# BioTempSch.net
KiCad netlist of a schematic drawn in Altium Designer
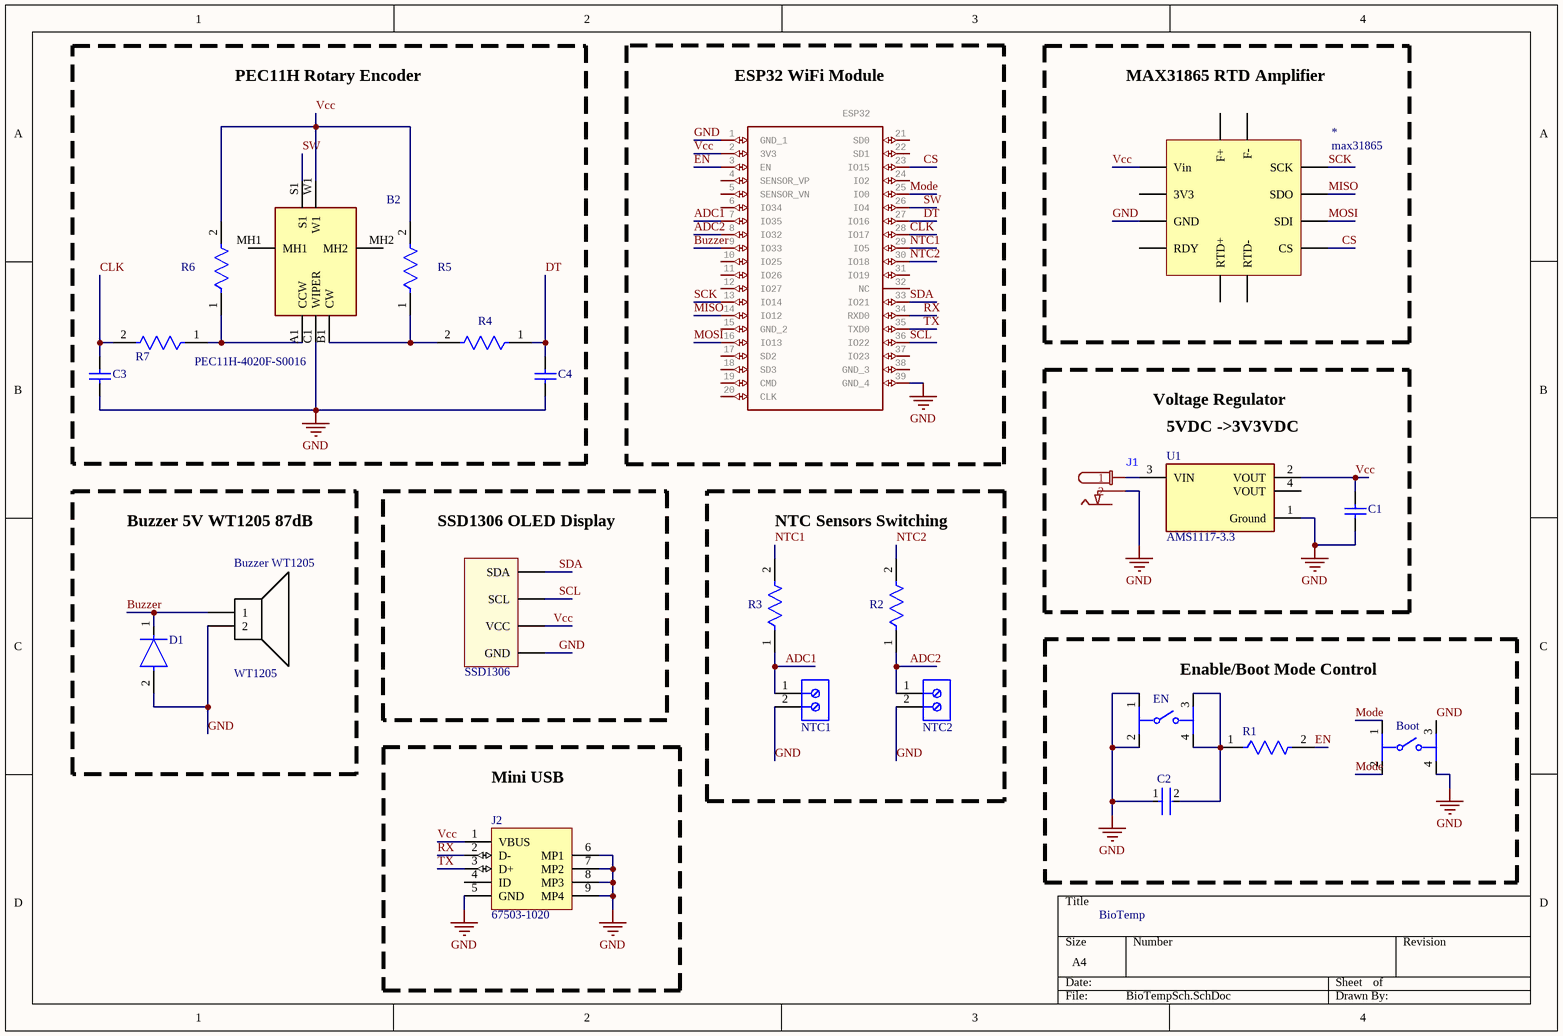
[diagram p0: BioTempSch.SchDoc]

(export (version "E")
  (design (tool "Eeschema 10.0.6"))
  (components
    (comp (ref "*")
      (value "max31865")
      (footprint "max31865")
      (libsource (lib "BioTempSchLib") (part "max31865"))
    )
    (comp (ref "B2")
      (value "PEC11H-4020F-S0016")
      (footprint "PEC11H4020FS0016")
      (description "Encoders ROTARY ENCODER W/BALL SPRING")
      (fields (field (name "MOUSER PART NUMBER") "652-PEC11H4020FS0016"))
      (libsource (lib "PEC11H-4020F-S0016") (part "PEC11H-4020F-S0016"))
    )
    (comp (ref "Boot")
      (value "B3F-1070")
      (footprint "FP-B3F-1070-MFG")
      (description "SWITCH TACTILE SPST-NO 0.05A 24V")
      (libsource (lib "Altium Content Vault") (part "b8895f3f4cefb76e1819d2863dba89b"))
    )
    (comp (ref "Buzzer WT1205")
      (value "WT1205")
      (footprint "WT1205")
      (description "Buzzer WT1205 87dB 5V")
      (libsource (lib "BioTempSchLib") (part "WT1205"))
    )
    (comp (ref "C1")
      (value "C0805C103K5RACTU")
      (footprint "CAPC2013X88X50LL20T25")
      (fields (field (name "MANUFACTURER") "Kemet"))
      (libsource (lib "Altium Content Vault") (part "CAP"))
    )
    (comp (ref "C2")
      (value "C0603C104M4RACTU")
      (footprint "FP-C0603C-CF-MFG")
      (description "CAP CER 0.1UF 16V X7R 0603")
      (fields (field (name "TOLERANCE") "0.2") (field (name "MANUFACTURER") "KEMET"))
      (libsource (lib "Altium Content Vault") (part "b4654b650e69147ec39a6b967a45e02"))
    )
    (comp (ref "C3")
      (value "C0805C103K5RACTU")
      (footprint "CAPC2013X88X50LL20T25")
      (fields (field (name "MANUFACTURER") "Kemet"))
      (libsource (lib "Altium Content Vault") (part "CAP"))
    )
    (comp (ref "C4")
      (value "C0805C103K5RACTU")
      (footprint "CAPC2013X88X50LL20T25")
      (fields (field (name "MANUFACTURER") "Kemet"))
      (libsource (lib "Altium Content Vault") (part "CAP"))
    )
    (comp (ref "D1")
      (value "1N4007 SMD")
      (footprint "FP-1N4007_SMD-IPC_C")
      (description "Rectifier, 1Kv, 1A, Do-214Ac Rohs Compliant: Yes")
      (libsource (lib "Altium Content Vault") (part "d7152d700b627762746794eb795d46e"))
    )
    (comp (ref "EN")
      (value "B3F-1070")
      (footprint "FP-B3F-1070-MFG")
      (description "SWITCH TACTILE SPST-NO 0.05A 24V")
      (libsource (lib "Altium Content Vault") (part "b8895f3f4cefb76e1819d2863dba89b"))
    )
    (comp (ref "ESP32")
      (value "WiFi Modules (802.11) SMD Module, ESP32-D0WD, 32Mbits SPI flash, UART mode, PCB antenna   Source:  Datasheet")
      (footprint "ESP32WROOM32D")
      (fields (field (name "MANUFACTURER_PART_NUMBER") "ESP32-WROOM-32D"))
      (libsource (lib "ESP32-WROOM-32D.Library") (part "ESP32-WROOM-32D"))
    )
    (comp (ref "J1")
      (value "~")
      (footprint "P4 JACK")
      (libsource (lib "altium-import") (part "root_0_POWER JACK P4_"))
    )
    (comp (ref "J2")
      (value "67503-1020")
      (footprint "MOLX-67503-1020_V")
      (description "USB, MINI, SMD, RA KME04-USBMU03A01")
      (fields (field (name "MANUFACTURER") "Molex"))
      (libsource (lib "Altium Content Vault") (part "MOLX-67503-1020"))
    )
    (comp (ref "NTC1")
      (value "691213710002")
      (footprint "691213710002")
      (fields (field (name "VOLTAGE") "300V"))
      (libsource (lib "Altium Content Vault") (part "TBL - 1R - 02P - Screw"))
    )
    (comp (ref "NTC2")
      (value "691213710002")
      (footprint "691213710002")
      (fields (field (name "VOLTAGE") "300V"))
      (libsource (lib "Altium Content Vault") (part "TBL - 1R - 02P - Screw"))
    )
    (comp (ref "R1")
      (value "RC0603FR-0710KL")
      (footprint "FP-RC0603-0_55-IPC_C")
      (description "RES 10K OHM 1% 1/10W 0603")
      (fields (field (name "TOLERANCE") "1%"))
      (libsource (lib "Altium Content Vault") (part "1029c3af85768c4190bb7ad29bc67b5"))
    )
    (comp (ref "R2")
      (value "RC0603FR-0710KL")
      (footprint "FP-RC0603-0_55-IPC_C")
      (description "RES 10K OHM 1% 1/10W 0603")
      (fields (field (name "TOLERANCE") "1%"))
      (libsource (lib "Altium Content Vault") (part "1029c3af85768c4190bb7ad29bc67b5"))
    )
    (comp (ref "R3")
      (value "RC0603FR-0710KL")
      (footprint "FP-RC0603-0_55-IPC_C")
      (description "RES 10K OHM 1% 1/10W 0603")
      (fields (field (name "TOLERANCE") "1%"))
      (libsource (lib "Altium Content Vault") (part "1029c3af85768c4190bb7ad29bc67b5"))
    )
    (comp (ref "R4")
      (value "RC0603FR-0710KL")
      (footprint "FP-RC0603-0_55-IPC_C")
      (description "RES 10K OHM 1% 1/10W 0603")
      (fields (field (name "TOLERANCE") "1%"))
      (libsource (lib "Altium Content Vault") (part "1029c3af85768c4190bb7ad29bc67b5"))
    )
    (comp (ref "R5")
      (value "RC0603FR-0710KL")
      (footprint "FP-RC0603-0_55-IPC_C")
      (description "RES 10K OHM 1% 1/10W 0603")
      (fields (field (name "TOLERANCE") "1%"))
      (libsource (lib "Altium Content Vault") (part "1029c3af85768c4190bb7ad29bc67b5"))
    )
    (comp (ref "R6")
      (value "RC0603FR-0710KL")
      (footprint "FP-RC0603-0_55-IPC_C")
      (description "RES 10K OHM 1% 1/10W 0603")
      (fields (field (name "TOLERANCE") "1%"))
      (libsource (lib "Altium Content Vault") (part "1029c3af85768c4190bb7ad29bc67b5"))
    )
    (comp (ref "R7")
      (value "RC0603FR-0710KL")
      (footprint "FP-RC0603-0_55-IPC_C")
      (description "RES 10K OHM 1% 1/10W 0603")
      (fields (field (name "TOLERANCE") "1%"))
      (libsource (lib "Altium Content Vault") (part "1029c3af85768c4190bb7ad29bc67b5"))
    )
    (comp (ref "SSD1306")
      (value "SSD1306")
      (footprint "SSD1306")
      (description "SSD1306 OLED Display 1280x64")
      (libsource (lib "BioTempSchLib") (part "SSD1306"))
    )
    (comp (ref "U1")
      (value "AMS1117-3.3")
      (footprint "FP-AMS1117-IPC_C")
      (description "LDO Voltage Regulators 1A, 3.3V")
      (fields
        (field (name "OCTOPART") "https://octopart.com/ams1117-3.3-advanced+monolithic+systems-25899300")
        (field (name "MANUFACTURER") "Advanced Monolithic Systems")
      )
      (libsource (lib "Altium Content Vault") (part "8bdbb5f8e77002000e30dd2845d0354"))
    )
  )
  (nets
    (net (code "1") (name "/ADC1") (class "Default")
      (node (ref "ESP32") (pin "7") (pinfunction "IO35_7") (pintype "bidirectional"))
      (node (ref "NTC1") (pin "1") (pinfunction "1_1") (pintype "passive"))
      (node (ref "R3") (pin "1") (pinfunction "1_1") (pintype "passive"))
    )
    (net (code "2") (name "/ADC2") (class "Default")
      (node (ref "ESP32") (pin "8") (pinfunction "IO32_8") (pintype "bidirectional"))
      (node (ref "NTC2") (pin "1") (pinfunction "1_1") (pintype "passive"))
      (node (ref "R2") (pin "1") (pinfunction "1_1") (pintype "passive"))
    )
    (net (code "3") (name "/Buzzer") (class "Default")
      (node (ref "Buzzer WT1205") (pin "1") (pinfunction "1_1") (pintype "passive"))
      (node (ref "D1") (pin "1") (pinfunction "C_1") (pintype "passive"))
      (node (ref "ESP32") (pin "9") (pinfunction "IO33_9") (pintype "bidirectional"))
    )
    (net (code "4") (name "/CLK") (class "Default")
      (node (ref "C3") (pin "2") (pinfunction "2_2") (pintype "passive"))
      (node (ref "ESP32") (pin "28") (pinfunction "IO17_28") (pintype "bidirectional"))
      (node (ref "R7") (pin "2") (pinfunction "2_2") (pintype "passive"))
    )
    (net (code "5") (name "/CS") (class "Default")
      (node (ref "*") (pin "7") (pinfunction "CS_7") (pintype "passive"))
      (node (ref "ESP32") (pin "23") (pinfunction "IO15_23") (pintype "bidirectional"))
    )
    (net (code "6") (name "/DT") (class "Default")
      (node (ref "C4") (pin "2") (pinfunction "2_2") (pintype "passive"))
      (node (ref "ESP32") (pin "27") (pinfunction "IO16_27") (pintype "bidirectional"))
      (node (ref "R4") (pin "1") (pinfunction "1_1") (pintype "passive"))
    )
    (net (code "7") (name "/EN") (class "Default")
      (node (ref "ESP32") (pin "3") (pinfunction "EN_3") (pintype "bidirectional"))
      (node (ref "R1") (pin "2") (pinfunction "2_2") (pintype "passive"))
    )
    (net (code "8") (name "/MISO") (class "Default")
      (node (ref "*") (pin "5") (pinfunction "SDO_5") (pintype "passive"))
      (node (ref "ESP32") (pin "14") (pinfunction "IO12_14") (pintype "bidirectional"))
    )
    (net (code "9") (name "/MOSI") (class "Default")
      (node (ref "*") (pin "6") (pinfunction "SDI_6") (pintype "passive"))
      (node (ref "ESP32") (pin "16") (pinfunction "IO13_16") (pintype "bidirectional"))
    )
    (net (code "10") (name "/Mode") (class "Default")
      (node (ref "Boot") (pin "1") (pinfunction "1_1") (pintype "passive"))
      (node (ref "Boot") (pin "2") (pinfunction "2_2") (pintype "passive"))
      (node (ref "ESP32") (pin "25") (pinfunction "IO0_25") (pintype "bidirectional"))
    )
    (net (code "11") (name "/NTC1") (class "Default")
      (node (ref "ESP32") (pin "29") (pinfunction "IO5_29") (pintype "bidirectional"))
      (node (ref "R3") (pin "2") (pinfunction "2_2") (pintype "passive"))
    )
    (net (code "12") (name "/NTC2") (class "Default")
      (node (ref "ESP32") (pin "30") (pinfunction "IO18_30") (pintype "bidirectional"))
      (node (ref "R2") (pin "2") (pinfunction "2_2") (pintype "passive"))
    )
    (net (code "13") (name "/RX") (class "Default")
      (node (ref "ESP32") (pin "34") (pinfunction "RXD0_34") (pintype "bidirectional"))
      (node (ref "J2") (pin "2") (pinfunction "D-_2") (pintype "bidirectional"))
    )
    (net (code "14") (name "/SCK") (class "Default")
      (node (ref "*") (pin "4") (pinfunction "SCK_4") (pintype "passive"))
      (node (ref "ESP32") (pin "13") (pinfunction "IO14_13") (pintype "bidirectional"))
    )
    (net (code "15") (name "/SCL") (class "Default")
      (node (ref "ESP32") (pin "36") (pinfunction "IO22_36") (pintype "bidirectional"))
      (node (ref "SSD1306") (pin "2") (pinfunction "SCL_2") (pintype "passive"))
    )
    (net (code "16") (name "/SDA") (class "Default")
      (node (ref "ESP32") (pin "33") (pinfunction "IO21_33") (pintype "bidirectional"))
      (node (ref "SSD1306") (pin "3") (pinfunction "SDA_3") (pintype "passive"))
    )
    (net (code "17") (name "/SW") (class "Default")
      (node (ref "B2") (pin "S1") (pinfunction "S1_S1") (pintype "passive"))
      (node (ref "ESP32") (pin "26") (pinfunction "IO4_26") (pintype "bidirectional"))
    )
    (net (code "18") (name "/TX") (class "Default")
      (node (ref "ESP32") (pin "35") (pinfunction "TXD0_35") (pintype "bidirectional"))
      (node (ref "J2") (pin "3") (pinfunction "D+_3") (pintype "bidirectional"))
    )
    (net (code "19") (name "/Vcc") (class "Default")
      (node (ref "*") (pin "1") (pinfunction "Vin_1") (pintype "passive"))
      (node (ref "B2") (pin "W1") (pinfunction "W1_W1") (pintype "passive"))
      (node (ref "C1") (pin "2") (pinfunction "2_2") (pintype "passive"))
      (node (ref "ESP32") (pin "2") (pinfunction "3V3_2") (pintype "bidirectional"))
      (node (ref "J2") (pin "1") (pinfunction "VBUS_1") (pintype "power_in"))
      (node (ref "R5") (pin "2") (pinfunction "2_2") (pintype "passive"))
      (node (ref "R6") (pin "2") (pinfunction "2_2") (pintype "passive"))
      (node (ref "SSD1306") (pin "1") (pinfunction "VCC_1") (pintype "passive"))
      (node (ref "U1") (pin "2") (pinfunction "VOUT_2") (pintype "passive"))
    )
    (net (code "20") (name "GND") (class "Default")
      (node (ref "*") (pin "2") (pinfunction "GND_2") (pintype "passive"))
      (node (ref "B2") (pin "C1") (pinfunction "WIPER_C1") (pintype "passive"))
      (node (ref "Boot") (pin "3") (pinfunction "3_3") (pintype "passive"))
      (node (ref "Boot") (pin "4") (pinfunction "4_4") (pintype "passive"))
      (node (ref "Buzzer WT1205") (pin "2") (pinfunction "2_2") (pintype "passive"))
      (node (ref "C1") (pin "1") (pinfunction "1_1") (pintype "passive"))
      (node (ref "C2") (pin "1") (pinfunction "1_1") (pintype "passive"))
      (node (ref "C3") (pin "1") (pinfunction "1_1") (pintype "passive"))
      (node (ref "C4") (pin "1") (pinfunction "1_1") (pintype "passive"))
      (node (ref "D1") (pin "2") (pinfunction "A_2") (pintype "passive"))
      (node (ref "EN") (pin "1") (pinfunction "1_1") (pintype "passive"))
      (node (ref "EN") (pin "2") (pinfunction "2_2") (pintype "passive"))
      (node (ref "ESP32") (pin "1") (pinfunction "GND_1_1") (pintype "bidirectional"))
      (node (ref "ESP32") (pin "39") (pinfunction "GND_4_39") (pintype "bidirectional"))
      (node (ref "J1") (pin "2") (pinfunction "2_2") (pintype "passive"))
      (node (ref "J2") (pin "5") (pinfunction "GND_5") (pintype "power_in"))
      (node (ref "J2") (pin "6") (pinfunction "MP1_6") (pintype "passive"))
      (node (ref "J2") (pin "7") (pinfunction "MP2_7") (pintype "passive"))
      (node (ref "J2") (pin "8") (pinfunction "MP3_8") (pintype "passive"))
      (node (ref "J2") (pin "9") (pinfunction "MP4_9") (pintype "passive"))
      (node (ref "NTC1") (pin "2") (pinfunction "2_2") (pintype "passive"))
      (node (ref "NTC2") (pin "2") (pinfunction "2_2") (pintype "passive"))
      (node (ref "SSD1306") (pin "0") (pinfunction "GND_0") (pintype "passive"))
      (node (ref "U1") (pin "1") (pinfunction "Ground_1") (pintype "power_in"))
    )
    (net (code "21") (name "Net-(B2-CCW)") (class "Default")
      (node (ref "B2") (pin "A1") (pinfunction "CCW_A1") (pintype "passive"))
      (node (ref "R6") (pin "1") (pinfunction "1_1") (pintype "passive"))
      (node (ref "R7") (pin "1") (pinfunction "1_1") (pintype "passive"))
    )
    (net (code "22") (name "Net-(B2-CW)") (class "Default")
      (node (ref "B2") (pin "B1") (pinfunction "CW_B1") (pintype "passive"))
      (node (ref "R4") (pin "2") (pinfunction "2_2") (pintype "passive"))
      (node (ref "R5") (pin "1") (pinfunction "1_1") (pintype "passive"))
    )
    (net (code "23") (name "Net-(C2-Pad2)") (class "Default")
      (node (ref "C2") (pin "2") (pinfunction "2_2") (pintype "passive"))
      (node (ref "EN") (pin "3") (pinfunction "3_3") (pintype "passive"))
      (node (ref "EN") (pin "4") (pinfunction "4_4") (pintype "passive"))
      (node (ref "R1") (pin "1") (pinfunction "1_1") (pintype "passive"))
    )
    (net (code "24") (name "Net-(U1-VIN)") (class "Default")
      (node (ref "J1") (pin "1") (pinfunction "1_1") (pintype "passive"))
      (node (ref "U1") (pin "3") (pinfunction "VIN_3") (pintype "power_in"))
    )
    (net (code "25") (name "unconnected-(*-3V3-Pad3)") (class "Default")
      (node (ref "*") (pin "3") (pinfunction "3V3_3") (pintype "passive"))
    )
    (net (code "26") (name "unconnected-(*-F+-Pad11)") (class "Default")
      (node (ref "*") (pin "11") (pinfunction "F+_11") (pintype "passive"))
    )
    (net (code "27") (name "unconnected-(*-F--Pad12)") (class "Default")
      (node (ref "*") (pin "12") (pinfunction "F-_12") (pintype "passive"))
    )
    (net (code "28") (name "unconnected-(*-RDY-Pad8)") (class "Default")
      (node (ref "*") (pin "8") (pinfunction "RDY_8") (pintype "passive"))
    )
    (net (code "29") (name "unconnected-(*-RTD+-Pad9)") (class "Default")
      (node (ref "*") (pin "9") (pinfunction "RTD+_9") (pintype "passive"))
    )
    (net (code "30") (name "unconnected-(*-RTD--Pad10)") (class "Default")
      (node (ref "*") (pin "10") (pinfunction "RTD-_10") (pintype "passive"))
    )
    (net (code "31") (name "unconnected-(B2-PadMH1)") (class "Default")
      (node (ref "B2") (pin "MH1") (pinfunction "MH1_MH1") (pintype "passive"))
    )
    (net (code "32") (name "unconnected-(B2-PadMH2)") (class "Default")
      (node (ref "B2") (pin "MH2") (pinfunction "MH2_MH2") (pintype "passive"))
    )
    (net (code "33") (name "unconnected-(ESP32-CLK-Pad20)") (class "Default")
      (node (ref "ESP32") (pin "20") (pinfunction "CLK_20") (pintype "bidirectional"))
    )
    (net (code "34") (name "unconnected-(ESP32-CMD-Pad19)") (class "Default")
      (node (ref "ESP32") (pin "19") (pinfunction "CMD_19") (pintype "bidirectional"))
    )
    (net (code "35") (name "unconnected-(ESP32-GND_2-Pad15)") (class "Default")
      (node (ref "ESP32") (pin "15") (pinfunction "GND_2_15") (pintype "bidirectional"))
    )
    (net (code "36") (name "unconnected-(ESP32-GND_3-Pad38)") (class "Default")
      (node (ref "ESP32") (pin "38") (pinfunction "GND_3_38") (pintype "bidirectional"))
    )
    (net (code "37") (name "unconnected-(ESP32-IO2-Pad24)") (class "Default")
      (node (ref "ESP32") (pin "24") (pinfunction "IO2_24") (pintype "bidirectional"))
    )
    (net (code "38") (name "unconnected-(ESP32-IO19-Pad31)") (class "Default")
      (node (ref "ESP32") (pin "31") (pinfunction "IO19_31") (pintype "bidirectional"))
    )
    (net (code "39") (name "unconnected-(ESP32-IO23-Pad37)") (class "Default")
      (node (ref "ESP32") (pin "37") (pinfunction "IO23_37") (pintype "bidirectional"))
    )
    (net (code "40") (name "unconnected-(ESP32-IO25-Pad10)") (class "Default")
      (node (ref "ESP32") (pin "10") (pinfunction "IO25_10") (pintype "bidirectional"))
    )
    (net (code "41") (name "unconnected-(ESP32-IO26-Pad11)") (class "Default")
      (node (ref "ESP32") (pin "11") (pinfunction "IO26_11") (pintype "bidirectional"))
    )
    (net (code "42") (name "unconnected-(ESP32-IO27-Pad12)") (class "Default")
      (node (ref "ESP32") (pin "12") (pinfunction "IO27_12") (pintype "bidirectional"))
    )
    (net (code "43") (name "unconnected-(ESP32-IO34-Pad6)") (class "Default")
      (node (ref "ESP32") (pin "6") (pinfunction "IO34_6") (pintype "bidirectional"))
    )
    (net (code "44") (name "unconnected-(ESP32-NC-Pad32)") (class "Default")
      (node (ref "ESP32") (pin "32") (pinfunction "NC_32") (pintype "passive"))
    )
    (net (code "45") (name "unconnected-(ESP32-SD0-Pad21)") (class "Default")
      (node (ref "ESP32") (pin "21") (pinfunction "SD0_21") (pintype "bidirectional"))
    )
    (net (code "46") (name "unconnected-(ESP32-SD1-Pad22)") (class "Default")
      (node (ref "ESP32") (pin "22") (pinfunction "SD1_22") (pintype "bidirectional"))
    )
    (net (code "47") (name "unconnected-(ESP32-SD2-Pad17)") (class "Default")
      (node (ref "ESP32") (pin "17") (pinfunction "SD2_17") (pintype "bidirectional"))
    )
    (net (code "48") (name "unconnected-(ESP32-SD3-Pad18)") (class "Default")
      (node (ref "ESP32") (pin "18") (pinfunction "SD3_18") (pintype "bidirectional"))
    )
    (net (code "49") (name "unconnected-(ESP32-SENSOR_VN-Pad5)") (class "Default")
      (node (ref "ESP32") (pin "5") (pinfunction "SENSOR_VN_5") (pintype "bidirectional"))
    )
    (net (code "50") (name "unconnected-(ESP32-SENSOR_VP-Pad4)") (class "Default")
      (node (ref "ESP32") (pin "4") (pinfunction "SENSOR_VP_4") (pintype "bidirectional"))
    )
    (net (code "51") (name "unconnected-(J2-ID-Pad4)") (class "Default")
      (node (ref "J2") (pin "4") (pinfunction "ID_4") (pintype "passive"))
    )
    (net (code "52") (name "unconnected-(U1-VOUT-Pad4)") (class "Default")
      (node (ref "U1") (pin "4") (pinfunction "VOUT_4") (pintype "passive"))
    )
  )
)
